# 11_Speak.net
KiCad netlist of a schematic drawn in Altium Designer
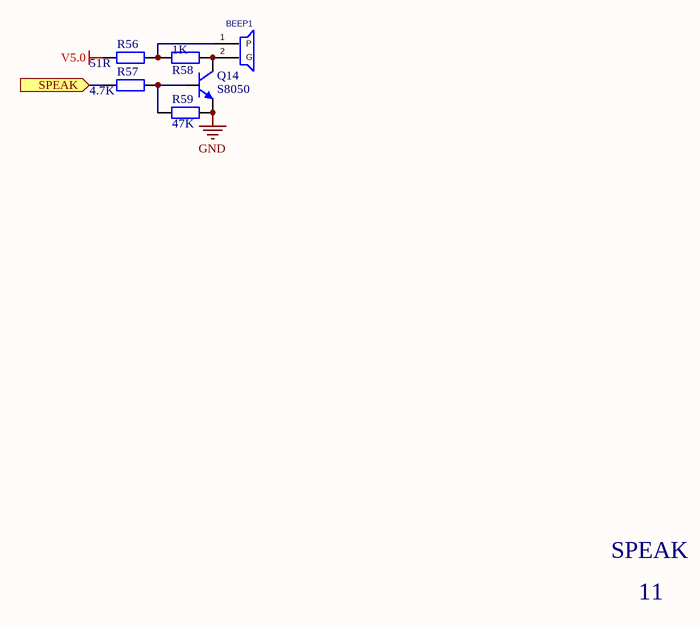
[diagram p0: 11_Speak.SchDoc]

(export (version "E")
  (design (tool "Eeschema 10.0.6"))
  (components
    (comp (ref "BEEP1")
      (value "BEEP-9.5X5.5")
      (footprint "BEEP-9.5X5.5")
      (libsource (lib "MINI-V3") (part "BEEP-9.5X5.5"))
    )
    (comp (ref "Q14")
      (value "S8050")
      (footprint "SOT-23")
      (description "NPN")
      (libsource (lib "XiaoyI") (part "NPN-1"))
    )
    (comp (ref "R56")
      (value "51R")
      (footprint "SMD-0603")
      (description "贴片电阻 5%")
      (libsource (lib "") (part "RES0_1"))
    )
    (comp (ref "R57")
      (value "4.7K")
      (footprint "SMD-0603")
      (description "贴片电阻 5%")
      (libsource (lib "ABB") (part "RES0"))
    )
    (comp (ref "R58")
      (value "1K")
      (footprint "SMD-0603")
      (description "贴片电阻 5%")
      (libsource (lib "") (part "RES0_1"))
    )
    (comp (ref "R59")
      (value "47K")
      (footprint "SMD-0603")
      (description "贴片电阻 5%")
      (libsource (lib "ABB") (part "RES0"))
    )
  )
  (nets
    (net (code "1") (name "/SPEAK") (class "Default")
      (node (ref "R57") (pin "1") (pinfunction "1_1") (pintype "passive"))
    )
    (net (code "2") (name "GND") (class "Default")
      (node (ref "Q14") (pin "2") (pinfunction "E_2") (pintype "passive"))
      (node (ref "R59") (pin "2") (pinfunction "2_2") (pintype "passive"))
    )
    (net (code "3") (name "Net-(BEEP1-G)") (class "Default")
      (node (ref "BEEP1") (pin "2") (pinfunction "G_2") (pintype "passive"))
      (node (ref "Q14") (pin "3") (pinfunction "C_3") (pintype "passive"))
      (node (ref "R58") (pin "1") (pinfunction "1_1") (pintype "passive"))
    )
    (net (code "4") (name "Net-(BEEP1-P)") (class "Default")
      (node (ref "BEEP1") (pin "1") (pinfunction "P_1") (pintype "passive"))
      (node (ref "R56") (pin "1") (pinfunction "1_1") (pintype "passive"))
      (node (ref "R58") (pin "2") (pinfunction "2_2") (pintype "passive"))
    )
    (net (code "5") (name "Net-(Q14-B)") (class "Default")
      (node (ref "Q14") (pin "1") (pinfunction "B_1") (pintype "passive"))
      (node (ref "R57") (pin "2") (pinfunction "2_2") (pintype "passive"))
      (node (ref "R59") (pin "1") (pinfunction "1_1") (pintype "passive"))
    )
    (net (code "6") (name "V5.0") (class "Default")
      (node (ref "R56") (pin "2") (pinfunction "2_2") (pintype "passive"))
    )
  )
)
